# mcb-enhancer-v2.net
KiCad netlist of a schematic drawn in EAGLE
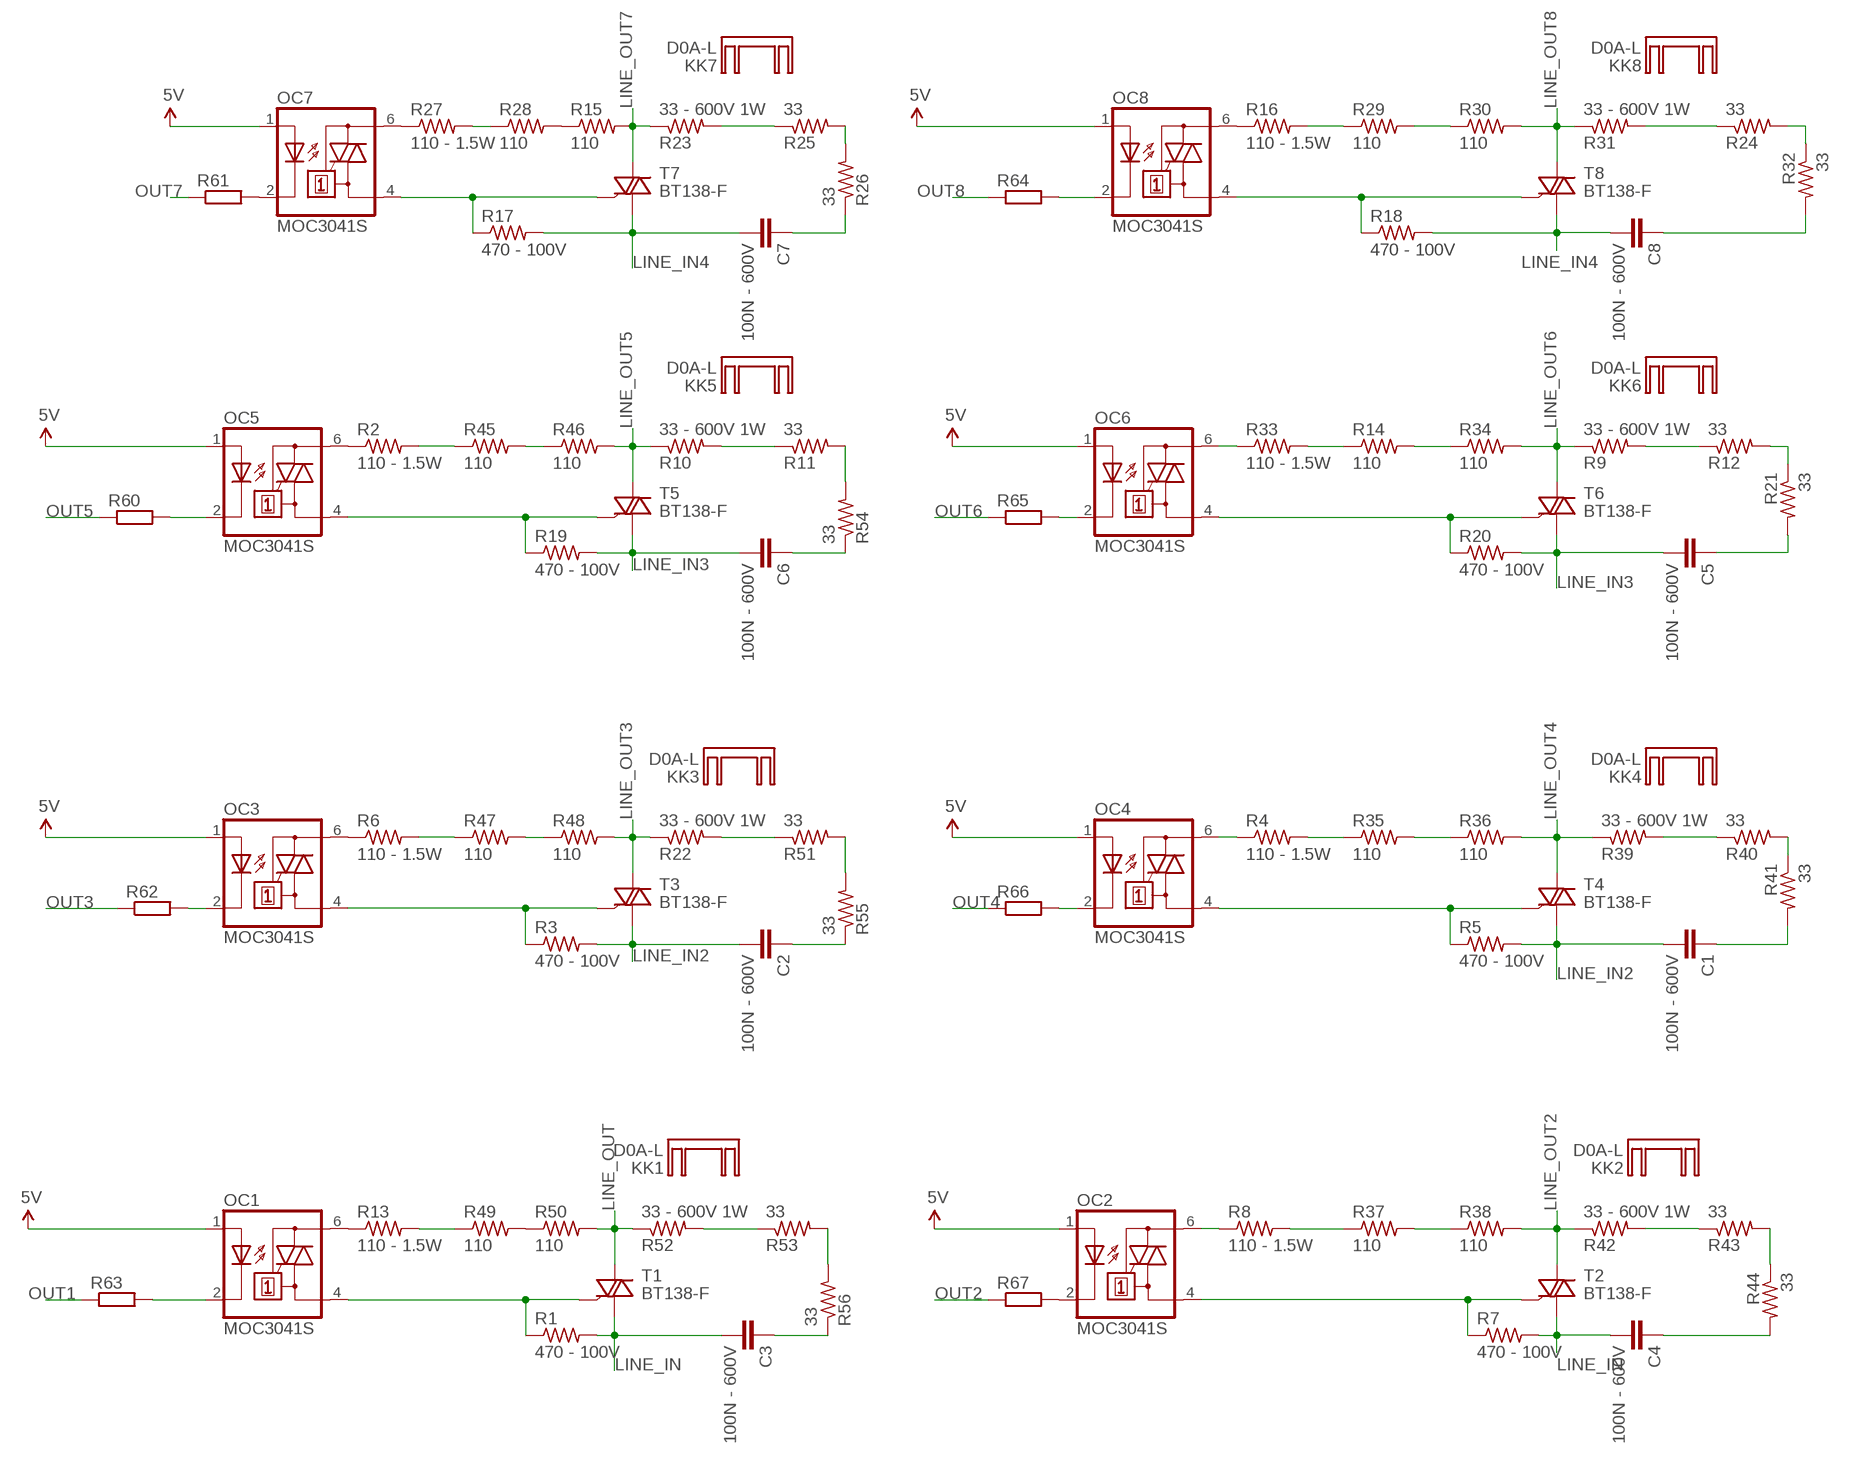
[diagram p0: schematic, sheet 1]

(export (version "E")
  (design (tool "Eeschema 10.0.6"))
  (components
    (comp (ref "C1")
      (value "100N - 600V")
      (footprint "eagle-import:C050-030X075")
      (libsource (lib "eagle-import") (part "C-EU050-030X075"))
    )
    (comp (ref "C2")
      (value "100N - 600V")
      (footprint "eagle-import:C050-030X075")
      (libsource (lib "eagle-import") (part "C-EU050-030X075"))
    )
    (comp (ref "C3")
      (value "100N - 600V")
      (footprint "eagle-import:C050-030X075")
      (libsource (lib "eagle-import") (part "C-EU050-030X075"))
    )
    (comp (ref "C4")
      (value "100N - 600V")
      (footprint "eagle-import:C050-030X075")
      (libsource (lib "eagle-import") (part "C-EU050-030X075"))
    )
    (comp (ref "C5")
      (value "100N - 600V")
      (footprint "eagle-import:C050-030X075")
      (libsource (lib "eagle-import") (part "C-EU050-030X075"))
    )
    (comp (ref "C6")
      (value "100N - 600V")
      (footprint "eagle-import:C050-030X075")
      (libsource (lib "eagle-import") (part "C-EU050-030X075"))
    )
    (comp (ref "C7")
      (value "100N - 600V")
      (footprint "eagle-import:C050-030X075")
      (libsource (lib "eagle-import") (part "C-EU050-030X075"))
    )
    (comp (ref "C8")
      (value "100N - 600V")
      (footprint "eagle-import:C050-030X075")
      (libsource (lib "eagle-import") (part "C-EU050-030X075"))
    )
    (comp (ref "KK1")
      (value "D0A-L")
      (footprint "eagle-import:D02A-L")
      (libsource (lib "eagle-import") (part "D0A-L"))
    )
    (comp (ref "KK2")
      (value "D0A-L")
      (footprint "eagle-import:D02A-L")
      (libsource (lib "eagle-import") (part "D0A-L"))
    )
    (comp (ref "KK3")
      (value "D0A-L")
      (footprint "eagle-import:D02A-L")
      (libsource (lib "eagle-import") (part "D0A-L"))
    )
    (comp (ref "KK4")
      (value "D0A-L")
      (footprint "eagle-import:D02A-L")
      (libsource (lib "eagle-import") (part "D0A-L"))
    )
    (comp (ref "KK5")
      (value "D0A-L")
      (footprint "eagle-import:D02A-L")
      (libsource (lib "eagle-import") (part "D0A-L"))
    )
    (comp (ref "KK6")
      (value "D0A-L")
      (footprint "eagle-import:D02A-L")
      (libsource (lib "eagle-import") (part "D0A-L"))
    )
    (comp (ref "KK7")
      (value "D0A-L")
      (footprint "eagle-import:D02A-L")
      (libsource (lib "eagle-import") (part "D0A-L"))
    )
    (comp (ref "KK8")
      (value "D0A-L")
      (footprint "eagle-import:D02A-L")
      (libsource (lib "eagle-import") (part "D0A-L"))
    )
    (comp (ref "OC1")
      (value "MOC3041S")
      (footprint "eagle-import:DIL6-SMD")
      (fields
        (field (name "MF") "FAIRCHILD SEMICONDUCTOR")
        (field (name "MPN") "MOC3041S-M")
        (field (name "MPN_1") "MOC3033S-M")
        (field (name "OC_FARNELL") "unknown")
        (field (name "OC_NEWARK") "05C2878")
      )
      (libsource (lib "eagle-import") (part "MOC30S41"))
    )
    (comp (ref "OC2")
      (value "MOC3041S")
      (footprint "eagle-import:DIL6-SMD")
      (fields
        (field (name "MF") "FAIRCHILD SEMICONDUCTOR")
        (field (name "MPN") "MOC3041S-M")
        (field (name "MPN_1") "MOC3033S-M")
        (field (name "OC_FARNELL") "unknown")
        (field (name "OC_NEWARK") "05C2878")
      )
      (libsource (lib "eagle-import") (part "MOC30S41"))
    )
    (comp (ref "OC3")
      (value "MOC3041S")
      (footprint "eagle-import:DIL6-SMD")
      (fields
        (field (name "MF") "FAIRCHILD SEMICONDUCTOR")
        (field (name "MPN") "MOC3041S-M")
        (field (name "MPN_1") "MOC3033S-M")
        (field (name "OC_FARNELL") "unknown")
        (field (name "OC_NEWARK") "05C2878")
      )
      (libsource (lib "eagle-import") (part "MOC30S41"))
    )
    (comp (ref "OC4")
      (value "MOC3041S")
      (footprint "eagle-import:DIL6-SMD")
      (fields
        (field (name "MF") "FAIRCHILD SEMICONDUCTOR")
        (field (name "MPN") "MOC3041S-M")
        (field (name "MPN_1") "MOC3033S-M")
        (field (name "OC_FARNELL") "unknown")
        (field (name "OC_NEWARK") "05C2878")
      )
      (libsource (lib "eagle-import") (part "MOC30S41"))
    )
    (comp (ref "OC5")
      (value "MOC3041S")
      (footprint "eagle-import:DIL6-SMD")
      (fields
        (field (name "MF") "FAIRCHILD SEMICONDUCTOR")
        (field (name "MPN") "MOC3041S-M")
        (field (name "MPN_1") "MOC3033S-M")
        (field (name "OC_FARNELL") "unknown")
        (field (name "OC_NEWARK") "05C2878")
      )
      (libsource (lib "eagle-import") (part "MOC30S41"))
    )
    (comp (ref "OC6")
      (value "MOC3041S")
      (footprint "eagle-import:DIL6-SMD")
      (fields
        (field (name "MF") "FAIRCHILD SEMICONDUCTOR")
        (field (name "MPN") "MOC3041S-M")
        (field (name "MPN_1") "MOC3033S-M")
        (field (name "OC_FARNELL") "unknown")
        (field (name "OC_NEWARK") "05C2878")
      )
      (libsource (lib "eagle-import") (part "MOC30S41"))
    )
    (comp (ref "OC7")
      (value "MOC3041S")
      (footprint "eagle-import:DIL6-SMD")
      (fields
        (field (name "MF") "FAIRCHILD SEMICONDUCTOR")
        (field (name "MPN") "MOC3041S-M")
        (field (name "MPN_1") "MOC3033S-M")
        (field (name "OC_FARNELL") "unknown")
        (field (name "OC_NEWARK") "05C2878")
      )
      (libsource (lib "eagle-import") (part "MOC30S41"))
    )
    (comp (ref "OC8")
      (value "MOC3041S")
      (footprint "eagle-import:DIL6-SMD")
      (fields
        (field (name "MF") "FAIRCHILD SEMICONDUCTOR")
        (field (name "MPN") "MOC3041S-M")
        (field (name "MPN_1") "MOC3033S-M")
        (field (name "OC_FARNELL") "unknown")
        (field (name "OC_NEWARK") "05C2878")
      )
      (libsource (lib "eagle-import") (part "MOC30S41"))
    )
    (comp (ref "R1")
      (value "470 - 100V")
      (footprint "eagle-import:M1206")
      (libsource (lib "eagle-import") (part "R-US_M1206"))
    )
    (comp (ref "R2")
      (value "110 - 1.5W")
      (footprint "eagle-import:R2512")
      (libsource (lib "eagle-import") (part "R-US_R2512"))
    )
    (comp (ref "R3")
      (value "470 - 100V")
      (footprint "eagle-import:M1206")
      (libsource (lib "eagle-import") (part "R-US_M1206"))
    )
    (comp (ref "R4")
      (value "110 - 1.5W")
      (footprint "eagle-import:R2512")
      (libsource (lib "eagle-import") (part "R-US_R2512"))
    )
    (comp (ref "R5")
      (value "470 - 100V")
      (footprint "eagle-import:M1206")
      (libsource (lib "eagle-import") (part "R-US_M1206"))
    )
    (comp (ref "R6")
      (value "110 - 1.5W")
      (footprint "eagle-import:R2512")
      (libsource (lib "eagle-import") (part "R-US_R2512"))
    )
    (comp (ref "R7")
      (value "470 - 100V")
      (footprint "eagle-import:M1206")
      (libsource (lib "eagle-import") (part "R-US_M1206"))
    )
    (comp (ref "R8")
      (value "110 - 1.5W")
      (footprint "eagle-import:R2512")
      (libsource (lib "eagle-import") (part "R-US_R2512"))
    )
    (comp (ref "R9")
      (value "33 - 600V 1W")
      (footprint "eagle-import:M1206")
      (libsource (lib "eagle-import") (part "R-US_M1206"))
    )
    (comp (ref "R10")
      (value "33 - 600V 1W")
      (footprint "eagle-import:M1206")
      (libsource (lib "eagle-import") (part "R-US_M1206"))
    )
    (comp (ref "R11")
      (value "33")
      (footprint "eagle-import:M1206")
      (libsource (lib "eagle-import") (part "R-US_M1206"))
    )
    (comp (ref "R12")
      (value "33")
      (footprint "eagle-import:M1206")
      (libsource (lib "eagle-import") (part "R-US_M1206"))
    )
    (comp (ref "R13")
      (value "110 - 1.5W")
      (footprint "eagle-import:R2512")
      (libsource (lib "eagle-import") (part "R-US_R2512"))
    )
    (comp (ref "R14")
      (value "110")
      (footprint "eagle-import:R2512")
      (libsource (lib "eagle-import") (part "R-US_R2512"))
    )
    (comp (ref "R15")
      (value "110")
      (footprint "eagle-import:R2512")
      (libsource (lib "eagle-import") (part "R-US_R2512"))
    )
    (comp (ref "R16")
      (value "110 - 1.5W")
      (footprint "eagle-import:R2512")
      (libsource (lib "eagle-import") (part "R-US_R2512"))
    )
    (comp (ref "R17")
      (value "470 - 100V")
      (footprint "eagle-import:M1206")
      (libsource (lib "eagle-import") (part "R-US_M1206"))
    )
    (comp (ref "R18")
      (value "470 - 100V")
      (footprint "eagle-import:M1206")
      (libsource (lib "eagle-import") (part "R-US_M1206"))
    )
    (comp (ref "R19")
      (value "470 - 100V")
      (footprint "eagle-import:M1206")
      (libsource (lib "eagle-import") (part "R-US_M1206"))
    )
    (comp (ref "R20")
      (value "470 - 100V")
      (footprint "eagle-import:M1206")
      (libsource (lib "eagle-import") (part "R-US_M1206"))
    )
    (comp (ref "R21")
      (value "33")
      (footprint "eagle-import:M1206")
      (libsource (lib "eagle-import") (part "R-US_M1206"))
    )
    (comp (ref "R22")
      (value "33 - 600V 1W")
      (footprint "eagle-import:M1206")
      (libsource (lib "eagle-import") (part "R-US_M1206"))
    )
    (comp (ref "R23")
      (value "33 - 600V 1W")
      (footprint "eagle-import:M1206")
      (libsource (lib "eagle-import") (part "R-US_M1206"))
    )
    (comp (ref "R24")
      (value "33")
      (footprint "eagle-import:M1206")
      (libsource (lib "eagle-import") (part "R-US_M1206"))
    )
    (comp (ref "R25")
      (value "33")
      (footprint "eagle-import:M1206")
      (libsource (lib "eagle-import") (part "R-US_M1206"))
    )
    (comp (ref "R26")
      (value "33")
      (footprint "eagle-import:M1206")
      (libsource (lib "eagle-import") (part "R-US_M1206"))
    )
    (comp (ref "R27")
      (value "110 - 1.5W")
      (footprint "eagle-import:R2512")
      (libsource (lib "eagle-import") (part "R-US_R2512"))
    )
    (comp (ref "R28")
      (value "110")
      (footprint "eagle-import:R2512")
      (libsource (lib "eagle-import") (part "R-US_R2512"))
    )
    (comp (ref "R29")
      (value "110")
      (footprint "eagle-import:R2512")
      (libsource (lib "eagle-import") (part "R-US_R2512"))
    )
    (comp (ref "R30")
      (value "110")
      (footprint "eagle-import:R2512")
      (libsource (lib "eagle-import") (part "R-US_R2512"))
    )
    (comp (ref "R31")
      (value "33 - 600V 1W")
      (footprint "eagle-import:M1206")
      (libsource (lib "eagle-import") (part "R-US_M1206"))
    )
    (comp (ref "R32")
      (value "33")
      (footprint "eagle-import:M1206")
      (libsource (lib "eagle-import") (part "R-US_M1206"))
    )
    (comp (ref "R33")
      (value "110 - 1.5W")
      (footprint "eagle-import:R2512")
      (libsource (lib "eagle-import") (part "R-US_R2512"))
    )
    (comp (ref "R34")
      (value "110")
      (footprint "eagle-import:R2512")
      (libsource (lib "eagle-import") (part "R-US_R2512"))
    )
    (comp (ref "R35")
      (value "110")
      (footprint "eagle-import:R2512")
      (libsource (lib "eagle-import") (part "R-US_R2512"))
    )
    (comp (ref "R36")
      (value "110")
      (footprint "eagle-import:R2512")
      (libsource (lib "eagle-import") (part "R-US_R2512"))
    )
    (comp (ref "R37")
      (value "110")
      (footprint "eagle-import:R2512")
      (libsource (lib "eagle-import") (part "R-US_R2512"))
    )
    (comp (ref "R38")
      (value "110")
      (footprint "eagle-import:R2512")
      (libsource (lib "eagle-import") (part "R-US_R2512"))
    )
    (comp (ref "R39")
      (value "33 - 600V 1W")
      (footprint "eagle-import:M1206")
      (libsource (lib "eagle-import") (part "R-US_M1206"))
    )
    (comp (ref "R40")
      (value "33")
      (footprint "eagle-import:M1206")
      (libsource (lib "eagle-import") (part "R-US_M1206"))
    )
    (comp (ref "R41")
      (value "33")
      (footprint "eagle-import:M1206")
      (libsource (lib "eagle-import") (part "R-US_M1206"))
    )
    (comp (ref "R42")
      (value "33 - 600V 1W")
      (footprint "eagle-import:M1206")
      (libsource (lib "eagle-import") (part "R-US_M1206"))
    )
    (comp (ref "R43")
      (value "33")
      (footprint "eagle-import:M1206")
      (libsource (lib "eagle-import") (part "R-US_M1206"))
    )
    (comp (ref "R44")
      (value "33")
      (footprint "eagle-import:M1206")
      (libsource (lib "eagle-import") (part "R-US_M1206"))
    )
    (comp (ref "R45")
      (value "110")
      (footprint "eagle-import:R2512")
      (libsource (lib "eagle-import") (part "R-US_R2512"))
    )
    (comp (ref "R46")
      (value "110")
      (footprint "eagle-import:R2512")
      (libsource (lib "eagle-import") (part "R-US_R2512"))
    )
    (comp (ref "R47")
      (value "110")
      (footprint "eagle-import:R2512")
      (libsource (lib "eagle-import") (part "R-US_R2512"))
    )
    (comp (ref "R48")
      (value "110")
      (footprint "eagle-import:R2512")
      (libsource (lib "eagle-import") (part "R-US_R2512"))
    )
    (comp (ref "R49")
      (value "110")
      (footprint "eagle-import:R2512")
      (libsource (lib "eagle-import") (part "R-US_R2512"))
    )
    (comp (ref "R50")
      (value "110")
      (footprint "eagle-import:R2512")
      (libsource (lib "eagle-import") (part "R-US_R2512"))
    )
    (comp (ref "R51")
      (value "33")
      (footprint "eagle-import:M1206")
      (libsource (lib "eagle-import") (part "R-US_M1206"))
    )
    (comp (ref "R52")
      (value "33 - 600V 1W")
      (footprint "eagle-import:M1206")
      (libsource (lib "eagle-import") (part "R-US_M1206"))
    )
    (comp (ref "R53")
      (value "33")
      (footprint "eagle-import:M1206")
      (libsource (lib "eagle-import") (part "R-US_M1206"))
    )
    (comp (ref "R54")
      (value "33")
      (footprint "eagle-import:M1206")
      (libsource (lib "eagle-import") (part "R-US_M1206"))
    )
    (comp (ref "R55")
      (value "33")
      (footprint "eagle-import:M1206")
      (libsource (lib "eagle-import") (part "R-US_M1206"))
    )
    (comp (ref "R56")
      (value "33")
      (footprint "eagle-import:M1206")
      (libsource (lib "eagle-import") (part "R-US_M1206"))
    )
    (comp (ref "R60")
      (value "R-EU_R0603")
      (footprint "eagle-import:R0603")
      (libsource (lib "eagle-import") (part "R-EU_R0603"))
    )
    (comp (ref "R61")
      (value "R-EU_R0603")
      (footprint "eagle-import:R0603")
      (libsource (lib "eagle-import") (part "R-EU_R0603"))
    )
    (comp (ref "R62")
      (value "R-EU_R0603")
      (footprint "eagle-import:R0603")
      (libsource (lib "eagle-import") (part "R-EU_R0603"))
    )
    (comp (ref "R63")
      (value "R-EU_R0603")
      (footprint "eagle-import:R0603")
      (libsource (lib "eagle-import") (part "R-EU_R0603"))
    )
    (comp (ref "R64")
      (value "R-EU_R0603")
      (footprint "eagle-import:R0603")
      (libsource (lib "eagle-import") (part "R-EU_R0603"))
    )
    (comp (ref "R65")
      (value "R-EU_R0603")
      (footprint "eagle-import:R0603")
      (libsource (lib "eagle-import") (part "R-EU_R0603"))
    )
    (comp (ref "R66")
      (value "R-EU_R0603")
      (footprint "eagle-import:R0603")
      (libsource (lib "eagle-import") (part "R-EU_R0603"))
    )
    (comp (ref "R67")
      (value "R-EU_R0603")
      (footprint "eagle-import:R0603")
      (libsource (lib "eagle-import") (part "R-EU_R0603"))
    )
    (comp (ref "T1")
      (value "BT138-F")
      (footprint "eagle-import:TO220BF")
      (libsource (lib "eagle-import") (part "BT138-F"))
    )
    (comp (ref "T2")
      (value "BT138-F")
      (footprint "eagle-import:TO220BF")
      (libsource (lib "eagle-import") (part "BT138-F"))
    )
    (comp (ref "T3")
      (value "BT138-F")
      (footprint "eagle-import:TO220BF")
      (libsource (lib "eagle-import") (part "BT138-F"))
    )
    (comp (ref "T4")
      (value "BT138-F")
      (footprint "eagle-import:TO220BF")
      (libsource (lib "eagle-import") (part "BT138-F"))
    )
    (comp (ref "T5")
      (value "BT138-F")
      (footprint "eagle-import:TO220BF")
      (libsource (lib "eagle-import") (part "BT138-F"))
    )
    (comp (ref "T6")
      (value "BT138-F")
      (footprint "eagle-import:TO220BF")
      (libsource (lib "eagle-import") (part "BT138-F"))
    )
    (comp (ref "T7")
      (value "BT138-F")
      (footprint "eagle-import:TO220BF")
      (libsource (lib "eagle-import") (part "BT138-F"))
    )
    (comp (ref "T8")
      (value "BT138-F")
      (footprint "eagle-import:TO220BF")
      (libsource (lib "eagle-import") (part "BT138-F"))
    )
  )
  (nets
    (net (code "1") (name "/LINE_IN") (class "Default")
      (node (ref "C3") (pin "2") (pinfunction "2_2") (pintype "passive"))
      (node (ref "C4") (pin "2") (pinfunction "2_2") (pintype "passive"))
      (node (ref "R1") (pin "2") (pinfunction "2_2") (pintype "passive"))
      (node (ref "R7") (pin "2") (pinfunction "2_2") (pintype "passive"))
      (node (ref "T1") (pin "T1") (pinfunction "A1_T1") (pintype "passive"))
      (node (ref "T2") (pin "T1") (pinfunction "A1_T1") (pintype "passive"))
    )
    (net (code "2") (name "/LINE_IN2") (class "Default")
      (node (ref "C1") (pin "2") (pinfunction "2_2") (pintype "passive"))
      (node (ref "C2") (pin "2") (pinfunction "2_2") (pintype "passive"))
      (node (ref "R3") (pin "2") (pinfunction "2_2") (pintype "passive"))
      (node (ref "R5") (pin "2") (pinfunction "2_2") (pintype "passive"))
      (node (ref "T3") (pin "T1") (pinfunction "A1_T1") (pintype "passive"))
      (node (ref "T4") (pin "T1") (pinfunction "A1_T1") (pintype "passive"))
    )
    (net (code "3") (name "/LINE_IN3") (class "Default")
      (node (ref "C5") (pin "2") (pinfunction "2_2") (pintype "passive"))
      (node (ref "C6") (pin "2") (pinfunction "2_2") (pintype "passive"))
      (node (ref "R19") (pin "2") (pinfunction "2_2") (pintype "passive"))
      (node (ref "R20") (pin "2") (pinfunction "2_2") (pintype "passive"))
      (node (ref "T5") (pin "T1") (pinfunction "A1_T1") (pintype "passive"))
      (node (ref "T6") (pin "T1") (pinfunction "A1_T1") (pintype "passive"))
    )
    (net (code "4") (name "/LINE_IN4") (class "Default")
      (node (ref "C7") (pin "2") (pinfunction "2_2") (pintype "passive"))
      (node (ref "C8") (pin "2") (pinfunction "2_2") (pintype "passive"))
      (node (ref "R17") (pin "2") (pinfunction "2_2") (pintype "passive"))
      (node (ref "R18") (pin "2") (pinfunction "2_2") (pintype "passive"))
      (node (ref "T7") (pin "T1") (pinfunction "A1_T1") (pintype "passive"))
      (node (ref "T8") (pin "T1") (pinfunction "A1_T1") (pintype "passive"))
    )
    (net (code "5") (name "/LINE_OUT") (class "Default")
      (node (ref "R50") (pin "2") (pinfunction "2_2") (pintype "passive"))
      (node (ref "R52") (pin "1") (pinfunction "1_1") (pintype "passive"))
      (node (ref "T1") (pin "T2") (pinfunction "A2_T2") (pintype "passive"))
    )
    (net (code "6") (name "/LINE_OUT2") (class "Default")
      (node (ref "R38") (pin "2") (pinfunction "2_2") (pintype "passive"))
      (node (ref "R42") (pin "1") (pinfunction "1_1") (pintype "passive"))
      (node (ref "T2") (pin "T2") (pinfunction "A2_T2") (pintype "passive"))
    )
    (net (code "7") (name "/LINE_OUT3") (class "Default")
      (node (ref "R22") (pin "1") (pinfunction "1_1") (pintype "passive"))
      (node (ref "R48") (pin "2") (pinfunction "2_2") (pintype "passive"))
      (node (ref "T3") (pin "T2") (pinfunction "A2_T2") (pintype "passive"))
    )
    (net (code "8") (name "/LINE_OUT4") (class "Default")
      (node (ref "R36") (pin "2") (pinfunction "2_2") (pintype "passive"))
      (node (ref "R39") (pin "1") (pinfunction "1_1") (pintype "passive"))
      (node (ref "T4") (pin "T2") (pinfunction "A2_T2") (pintype "passive"))
    )
    (net (code "9") (name "/LINE_OUT5") (class "Default")
      (node (ref "R10") (pin "1") (pinfunction "1_1") (pintype "passive"))
      (node (ref "R46") (pin "2") (pinfunction "2_2") (pintype "passive"))
      (node (ref "T5") (pin "T2") (pinfunction "A2_T2") (pintype "passive"))
    )
    (net (code "10") (name "/LINE_OUT6") (class "Default")
      (node (ref "R34") (pin "2") (pinfunction "2_2") (pintype "passive"))
      (node (ref "R9") (pin "1") (pinfunction "1_1") (pintype "passive"))
      (node (ref "T6") (pin "T2") (pinfunction "A2_T2") (pintype "passive"))
    )
    (net (code "11") (name "/LINE_OUT7") (class "Default")
      (node (ref "R15") (pin "2") (pinfunction "2_2") (pintype "passive"))
      (node (ref "R23") (pin "1") (pinfunction "1_1") (pintype "passive"))
      (node (ref "T7") (pin "T2") (pinfunction "A2_T2") (pintype "passive"))
    )
    (net (code "12") (name "/LINE_OUT8") (class "Default")
      (node (ref "R30") (pin "2") (pinfunction "2_2") (pintype "passive"))
      (node (ref "R31") (pin "1") (pinfunction "1_1") (pintype "passive"))
      (node (ref "T8") (pin "T2") (pinfunction "A2_T2") (pintype "passive"))
    )
    (net (code "13") (name "/OUT1") (class "Default")
      (node (ref "R63") (pin "1") (pinfunction "1_1") (pintype "passive"))
    )
    (net (code "14") (name "/OUT2") (class "Default")
      (node (ref "R67") (pin "1") (pinfunction "1_1") (pintype "passive"))
    )
    (net (code "15") (name "/OUT3") (class "Default")
      (node (ref "R62") (pin "1") (pinfunction "1_1") (pintype "passive"))
    )
    (net (code "16") (name "/OUT4") (class "Default")
      (node (ref "R66") (pin "1") (pinfunction "1_1") (pintype "passive"))
    )
    (net (code "17") (name "/OUT5") (class "Default")
      (node (ref "R60") (pin "1") (pinfunction "1_1") (pintype "passive"))
    )
    (net (code "18") (name "/OUT6") (class "Default")
      (node (ref "R65") (pin "1") (pinfunction "1_1") (pintype "passive"))
    )
    (net (code "19") (name "/OUT7") (class "Default")
      (node (ref "R61") (pin "1") (pinfunction "1_1") (pintype "passive"))
    )
    (net (code "20") (name "/OUT8") (class "Default")
      (node (ref "R64") (pin "1") (pinfunction "1_1") (pintype "passive"))
    )
    (net (code "21") (name "5V") (class "Default")
      (node (ref "OC1") (pin "1") (pinfunction "A_1") (pintype "passive"))
      (node (ref "OC2") (pin "1") (pinfunction "A_1") (pintype "passive"))
      (node (ref "OC3") (pin "1") (pinfunction "A_1") (pintype "passive"))
      (node (ref "OC4") (pin "1") (pinfunction "A_1") (pintype "passive"))
      (node (ref "OC5") (pin "1") (pinfunction "A_1") (pintype "passive"))
      (node (ref "OC6") (pin "1") (pinfunction "A_1") (pintype "passive"))
      (node (ref "OC7") (pin "1") (pinfunction "A_1") (pintype "passive"))
      (node (ref "OC8") (pin "1") (pinfunction "A_1") (pintype "passive"))
    )
    (net (code "22") (name "Net-(C1-Pad1)") (class "Default")
      (node (ref "C1") (pin "1") (pinfunction "1_1") (pintype "passive"))
      (node (ref "R41") (pin "2") (pinfunction "2_2") (pintype "passive"))
    )
    (net (code "23") (name "Net-(C2-Pad1)") (class "Default")
      (node (ref "C2") (pin "1") (pinfunction "1_1") (pintype "passive"))
      (node (ref "R55") (pin "1") (pinfunction "1_1") (pintype "passive"))
    )
    (net (code "24") (name "Net-(C3-Pad1)") (class "Default")
      (node (ref "C3") (pin "1") (pinfunction "1_1") (pintype "passive"))
      (node (ref "R56") (pin "1") (pinfunction "1_1") (pintype "passive"))
    )
    (net (code "25") (name "Net-(C4-Pad1)") (class "Default")
      (node (ref "C4") (pin "1") (pinfunction "1_1") (pintype "passive"))
      (node (ref "R44") (pin "2") (pinfunction "2_2") (pintype "passive"))
    )
    (net (code "26") (name "Net-(C5-Pad1)") (class "Default")
      (node (ref "C5") (pin "1") (pinfunction "1_1") (pintype "passive"))
      (node (ref "R21") (pin "2") (pinfunction "2_2") (pintype "passive"))
    )
    (net (code "27") (name "Net-(C6-Pad1)") (class "Default")
      (node (ref "C6") (pin "1") (pinfunction "1_1") (pintype "passive"))
      (node (ref "R54") (pin "1") (pinfunction "1_1") (pintype "passive"))
    )
    (net (code "28") (name "Net-(C7-Pad1)") (class "Default")
      (node (ref "C7") (pin "1") (pinfunction "1_1") (pintype "passive"))
      (node (ref "R26") (pin "1") (pinfunction "1_1") (pintype "passive"))
    )
    (net (code "29") (name "Net-(C8-Pad1)") (class "Default")
      (node (ref "C8") (pin "1") (pinfunction "1_1") (pintype "passive"))
      (node (ref "R32") (pin "2") (pinfunction "2_2") (pintype "passive"))
    )
    (net (code "30") (name "Net-(OC1-A1)") (class "Default")
      (node (ref "OC1") (pin "4") (pinfunction "A1_4") (pintype "passive"))
      (node (ref "R1") (pin "1") (pinfunction "1_1") (pintype "passive"))
      (node (ref "T1") (pin "G") (pinfunction "G_G") (pintype "passive"))
    )
    (net (code "31") (name "Net-(OC1-A2)") (class "Default")
      (node (ref "OC1") (pin "6") (pinfunction "A2_6") (pintype "passive"))
      (node (ref "R13") (pin "1") (pinfunction "1_1") (pintype "passive"))
    )
    (net (code "32") (name "Net-(OC1-C)") (class "Default")
      (node (ref "OC1") (pin "2") (pinfunction "C_2") (pintype "passive"))
      (node (ref "R63") (pin "2") (pinfunction "2_2") (pintype "passive"))
    )
    (net (code "33") (name "Net-(OC2-A1)") (class "Default")
      (node (ref "OC2") (pin "4") (pinfunction "A1_4") (pintype "passive"))
      (node (ref "R7") (pin "1") (pinfunction "1_1") (pintype "passive"))
      (node (ref "T2") (pin "G") (pinfunction "G_G") (pintype "passive"))
    )
    (net (code "34") (name "Net-(OC2-A2)") (class "Default")
      (node (ref "OC2") (pin "6") (pinfunction "A2_6") (pintype "passive"))
      (node (ref "R8") (pin "1") (pinfunction "1_1") (pintype "passive"))
    )
    (net (code "35") (name "Net-(OC2-C)") (class "Default")
      (node (ref "OC2") (pin "2") (pinfunction "C_2") (pintype "passive"))
      (node (ref "R67") (pin "2") (pinfunction "2_2") (pintype "passive"))
    )
    (net (code "36") (name "Net-(OC3-A1)") (class "Default")
      (node (ref "OC3") (pin "4") (pinfunction "A1_4") (pintype "passive"))
      (node (ref "R3") (pin "1") (pinfunction "1_1") (pintype "passive"))
      (node (ref "T3") (pin "G") (pinfunction "G_G") (pintype "passive"))
    )
    (net (code "37") (name "Net-(OC3-A2)") (class "Default")
      (node (ref "OC3") (pin "6") (pinfunction "A2_6") (pintype "passive"))
      (node (ref "R6") (pin "1") (pinfunction "1_1") (pintype "passive"))
    )
    (net (code "38") (name "Net-(OC3-C)") (class "Default")
      (node (ref "OC3") (pin "2") (pinfunction "C_2") (pintype "passive"))
      (node (ref "R62") (pin "2") (pinfunction "2_2") (pintype "passive"))
    )
    (net (code "39") (name "Net-(OC4-A1)") (class "Default")
      (node (ref "OC4") (pin "4") (pinfunction "A1_4") (pintype "passive"))
      (node (ref "R5") (pin "1") (pinfunction "1_1") (pintype "passive"))
      (node (ref "T4") (pin "G") (pinfunction "G_G") (pintype "passive"))
    )
    (net (code "40") (name "Net-(OC4-A2)") (class "Default")
      (node (ref "OC4") (pin "6") (pinfunction "A2_6") (pintype "passive"))
      (node (ref "R4") (pin "1") (pinfunction "1_1") (pintype "passive"))
    )
    (net (code "41") (name "Net-(OC4-C)") (class "Default")
      (node (ref "OC4") (pin "2") (pinfunction "C_2") (pintype "passive"))
      (node (ref "R66") (pin "2") (pinfunction "2_2") (pintype "passive"))
    )
    (net (code "42") (name "Net-(OC5-A1)") (class "Default")
      (node (ref "OC5") (pin "4") (pinfunction "A1_4") (pintype "passive"))
      (node (ref "R19") (pin "1") (pinfunction "1_1") (pintype "passive"))
      (node (ref "T5") (pin "G") (pinfunction "G_G") (pintype "passive"))
    )
    (net (code "43") (name "Net-(OC5-A2)") (class "Default")
      (node (ref "OC5") (pin "6") (pinfunction "A2_6") (pintype "passive"))
      (node (ref "R2") (pin "1") (pinfunction "1_1") (pintype "passive"))
    )
    (net (code "44") (name "Net-(OC5-C)") (class "Default")
      (node (ref "OC5") (pin "2") (pinfunction "C_2") (pintype "passive"))
      (node (ref "R60") (pin "2") (pinfunction "2_2") (pintype "passive"))
    )
    (net (code "45") (name "Net-(OC6-A1)") (class "Default")
      (node (ref "OC6") (pin "4") (pinfunction "A1_4") (pintype "passive"))
      (node (ref "R20") (pin "1") (pinfunction "1_1") (pintype "passive"))
      (node (ref "T6") (pin "G") (pinfunction "G_G") (pintype "passive"))
    )
    (net (code "46") (name "Net-(OC6-A2)") (class "Default")
      (node (ref "OC6") (pin "6") (pinfunction "A2_6") (pintype "passive"))
      (node (ref "R33") (pin "1") (pinfunction "1_1") (pintype "passive"))
    )
    (net (code "47") (name "Net-(OC6-C)") (class "Default")
      (node (ref "OC6") (pin "2") (pinfunction "C_2") (pintype "passive"))
      (node (ref "R65") (pin "2") (pinfunction "2_2") (pintype "passive"))
    )
    (net (code "48") (name "Net-(OC7-A1)") (class "Default")
      (node (ref "OC7") (pin "4") (pinfunction "A1_4") (pintype "passive"))
      (node (ref "R17") (pin "1") (pinfunction "1_1") (pintype "passive"))
      (node (ref "T7") (pin "G") (pinfunction "G_G") (pintype "passive"))
    )
    (net (code "49") (name "Net-(OC7-A2)") (class "Default")
      (node (ref "OC7") (pin "6") (pinfunction "A2_6") (pintype "passive"))
      (node (ref "R27") (pin "1") (pinfunction "1_1") (pintype "passive"))
    )
    (net (code "50") (name "Net-(OC7-C)") (class "Default")
      (node (ref "OC7") (pin "2") (pinfunction "C_2") (pintype "passive"))
      (node (ref "R61") (pin "2") (pinfunction "2_2") (pintype "passive"))
    )
    (net (code "51") (name "Net-(OC8-A1)") (class "Default")
      (node (ref "OC8") (pin "4") (pinfunction "A1_4") (pintype "passive"))
      (node (ref "R18") (pin "1") (pinfunction "1_1") (pintype "passive"))
      (node (ref "T8") (pin "G") (pinfunction "G_G") (pintype "passive"))
    )
    (net (code "52") (name "Net-(OC8-A2)") (class "Default")
      (node (ref "OC8") (pin "6") (pinfunction "A2_6") (pintype "passive"))
      (node (ref "R16") (pin "1") (pinfunction "1_1") (pintype "passive"))
    )
    (net (code "53") (name "Net-(OC8-C)") (class "Default")
      (node (ref "OC8") (pin "2") (pinfunction "C_2") (pintype "passive"))
      (node (ref "R64") (pin "2") (pinfunction "2_2") (pintype "passive"))
    )
    (net (code "54") (name "Net-(R2-Pad2)") (class "Default")
      (node (ref "R2") (pin "2") (pinfunction "2_2") (pintype "passive"))
      (node (ref "R45") (pin "1") (pinfunction "1_1") (pintype "passive"))
    )
    (net (code "55") (name "Net-(R10-Pad2)") (class "Default")
      (node (ref "R10") (pin "2") (pinfunction "2_2") (pintype "passive"))
      (node (ref "R11") (pin "1") (pinfunction "1_1") (pintype "passive"))
    )
    (net (code "56") (name "Net-(R11-Pad2)") (class "Default")
      (node (ref "R11") (pin "2") (pinfunction "2_2") (pintype "passive"))
      (node (ref "R54") (pin "2") (pinfunction "2_2") (pintype "passive"))
    )
    (net (code "57") (name "Net-(R12-Pad1)") (class "Default")
      (node (ref "R12") (pin "1") (pinfunction "1_1") (pintype "passive"))
      (node (ref "R9") (pin "2") (pinfunction "2_2") (pintype "passive"))
    )
    (net (code "58") (name "Net-(R12-Pad2)") (class "Default")
      (node (ref "R12") (pin "2") (pinfunction "2_2") (pintype "passive"))
      (node (ref "R21") (pin "1") (pinfunction "1_1") (pintype "passive"))
    )
    (net (code "59") (name "Net-(R13-Pad2)") (class "Default")
      (node (ref "R13") (pin "2") (pinfunction "2_2") (pintype "passive"))
      (node (ref "R49") (pin "1") (pinfunction "1_1") (pintype "passive"))
    )
    (net (code "60") (name "Net-(R14-Pad1)") (class "Default")
      (node (ref "R14") (pin "1") (pinfunction "1_1") (pintype "passive"))
      (node (ref "R33") (pin "2") (pinfunction "2_2") (pintype "passive"))
    )
    (net (code "61") (name "Net-(R14-Pad2)") (class "Default")
      (node (ref "R14") (pin "2") (pinfunction "2_2") (pintype "passive"))
      (node (ref "R34") (pin "1") (pinfunction "1_1") (pintype "passive"))
    )
    (net (code "62") (name "Net-(R15-Pad1)") (class "Default")
      (node (ref "R15") (pin "1") (pinfunction "1_1") (pintype "passive"))
      (node (ref "R28") (pin "2") (pinfunction "2_2") (pintype "passive"))
    )
    (net (code "63") (name "Net-(R16-Pad2)") (class "Default")
      (node (ref "R16") (pin "2") (pinfunction "2_2") (pintype "passive"))
      (node (ref "R29") (pin "1") (pinfunction "1_1") (pintype "passive"))
    )
    (net (code "64") (name "Net-(R22-Pad2)") (class "Default")
      (node (ref "R22") (pin "2") (pinfunction "2_2") (pintype "passive"))
      (node (ref "R51") (pin "1") (pinfunction "1_1") (pintype "passive"))
    )
    (net (code "65") (name "Net-(R23-Pad2)") (class "Default")
      (node (ref "R23") (pin "2") (pinfunction "2_2") (pintype "passive"))
      (node (ref "R25") (pin "1") (pinfunction "1_1") (pintype "passive"))
    )
    (net (code "66") (name "Net-(R24-Pad1)") (class "Default")
      (node (ref "R24") (pin "1") (pinfunction "1_1") (pintype "passive"))
      (node (ref "R31") (pin "2") (pinfunction "2_2") (pintype "passive"))
    )
    (net (code "67") (name "Net-(R24-Pad2)") (class "Default")
      (node (ref "R24") (pin "2") (pinfunction "2_2") (pintype "passive"))
      (node (ref "R32") (pin "1") (pinfunction "1_1") (pintype "passive"))
    )
    (net (code "68") (name "Net-(R25-Pad2)") (class "Default")
      (node (ref "R25") (pin "2") (pinfunction "2_2") (pintype "passive"))
      (node (ref "R26") (pin "2") (pinfunction "2_2") (pintype "passive"))
    )
    (net (code "69") (name "Net-(R27-Pad2)") (class "Default")
      (node (ref "R27") (pin "2") (pinfunction "2_2") (pintype "passive"))
      (node (ref "R28") (pin "1") (pinfunction "1_1") (pintype "passive"))
    )
    (net (code "70") (name "Net-(R29-Pad2)") (class "Default")
      (node (ref "R29") (pin "2") (pinfunction "2_2") (pintype "passive"))
      (node (ref "R30") (pin "1") (pinfunction "1_1") (pintype "passive"))
    )
    (net (code "71") (name "Net-(R35-Pad1)") (class "Default")
      (node (ref "R35") (pin "1") (pinfunction "1_1") (pintype "passive"))
      (node (ref "R4") (pin "2") (pinfunction "2_2") (pintype "passive"))
    )
    (net (code "72") (name "Net-(R35-Pad2)") (class "Default")
      (node (ref "R35") (pin "2") (pinfunction "2_2") (pintype "passive"))
      (node (ref "R36") (pin "1") (pinfunction "1_1") (pintype "passive"))
    )
    (net (code "73") (name "Net-(R37-Pad1)") (class "Default")
      (node (ref "R37") (pin "1") (pinfunction "1_1") (pintype "passive"))
      (node (ref "R8") (pin "2") (pinfunction "2_2") (pintype "passive"))
    )
    (net (code "74") (name "Net-(R37-Pad2)") (class "Default")
      (node (ref "R37") (pin "2") (pinfunction "2_2") (pintype "passive"))
      (node (ref "R38") (pin "1") (pinfunction "1_1") (pintype "passive"))
    )
    (net (code "75") (name "Net-(R39-Pad2)") (class "Default")
      (node (ref "R39") (pin "2") (pinfunction "2_2") (pintype "passive"))
      (node (ref "R40") (pin "1") (pinfunction "1_1") (pintype "passive"))
    )
    (net (code "76") (name "Net-(R40-Pad2)") (class "Default")
      (node (ref "R40") (pin "2") (pinfunction "2_2") (pintype "passive"))
      (node (ref "R41") (pin "1") (pinfunction "1_1") (pintype "passive"))
    )
    (net (code "77") (name "Net-(R42-Pad2)") (class "Default")
      (node (ref "R42") (pin "2") (pinfunction "2_2") (pintype "passive"))
      (node (ref "R43") (pin "1") (pinfunction "1_1") (pintype "passive"))
    )
    (net (code "78") (name "Net-(R43-Pad2)") (class "Default")
      (node (ref "R43") (pin "2") (pinfunction "2_2") (pintype "passive"))
      (node (ref "R44") (pin "1") (pinfunction "1_1") (pintype "passive"))
    )
    (net (code "79") (name "Net-(R45-Pad2)") (class "Default")
      (node (ref "R45") (pin "2") (pinfunction "2_2") (pintype "passive"))
      (node (ref "R46") (pin "1") (pinfunction "1_1") (pintype "passive"))
    )
    (net (code "80") (name "Net-(R47-Pad1)") (class "Default")
      (node (ref "R47") (pin "1") (pinfunction "1_1") (pintype "passive"))
      (node (ref "R6") (pin "2") (pinfunction "2_2") (pintype "passive"))
    )
    (net (code "81") (name "Net-(R47-Pad2)") (class "Default")
      (node (ref "R47") (pin "2") (pinfunction "2_2") (pintype "passive"))
      (node (ref "R48") (pin "1") (pinfunction "1_1") (pintype "passive"))
    )
    (net (code "82") (name "Net-(R49-Pad2)") (class "Default")
      (node (ref "R49") (pin "2") (pinfunction "2_2") (pintype "passive"))
      (node (ref "R50") (pin "1") (pinfunction "1_1") (pintype "passive"))
    )
    (net (code "83") (name "Net-(R51-Pad2)") (class "Default")
      (node (ref "R51") (pin "2") (pinfunction "2_2") (pintype "passive"))
      (node (ref "R55") (pin "2") (pinfunction "2_2") (pintype "passive"))
    )
    (net (code "84") (name "Net-(R52-Pad2)") (class "Default")
      (node (ref "R52") (pin "2") (pinfunction "2_2") (pintype "passive"))
      (node (ref "R53") (pin "1") (pinfunction "1_1") (pintype "passive"))
    )
    (net (code "85") (name "Net-(R53-Pad2)") (class "Default")
      (node (ref "R53") (pin "2") (pinfunction "2_2") (pintype "passive"))
      (node (ref "R56") (pin "2") (pinfunction "2_2") (pintype "passive"))
    )
  )
)
